# 05_CIS.net
KiCad netlist of a schematic drawn in Altium Designer
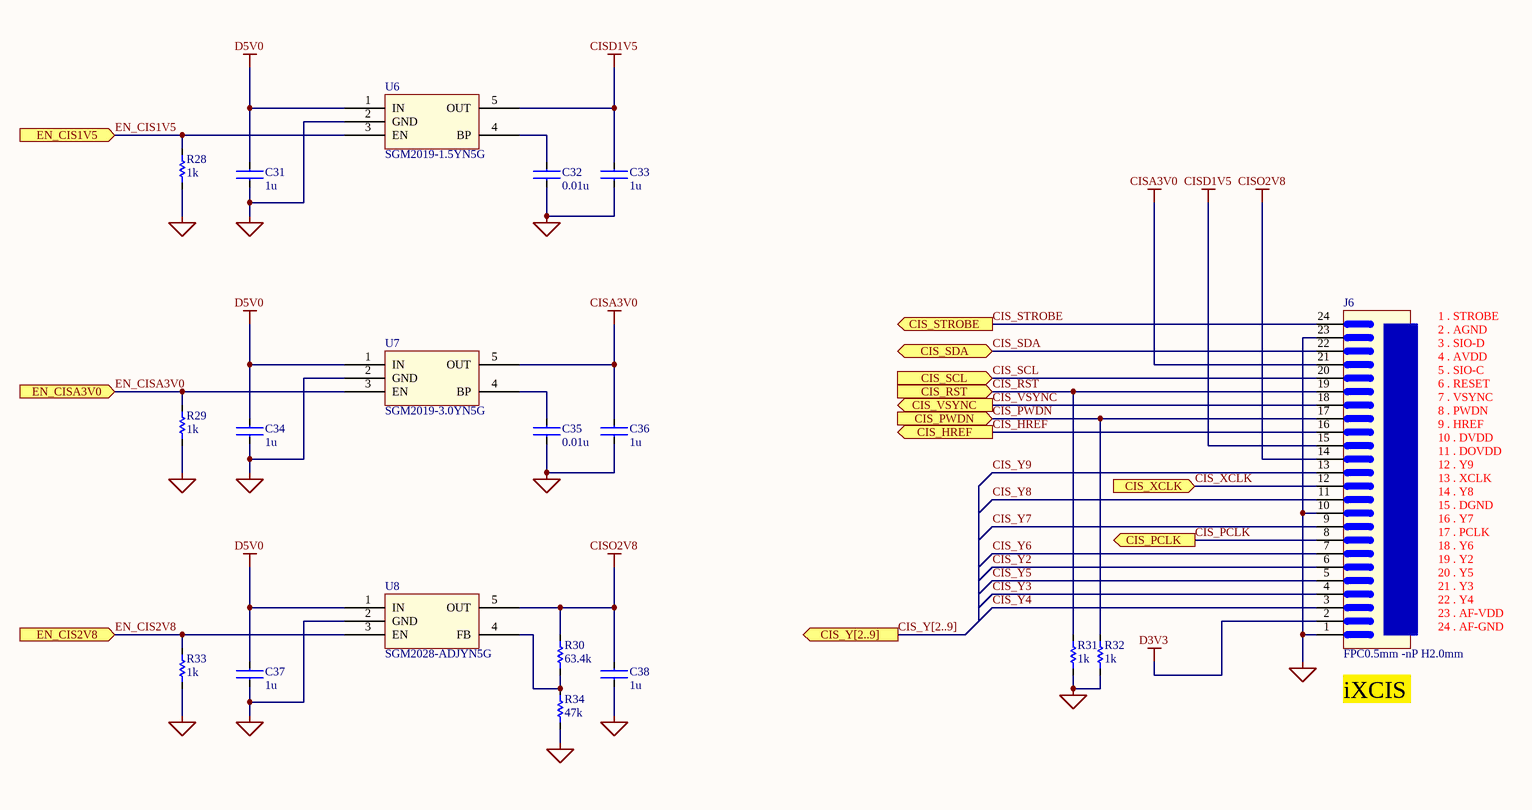
[diagram p0: 05_CIS.SchDoc]

(export (version "E")
  (design (tool "Eeschema 10.0.6"))
  (components
    (comp (ref "C31")
      (value "1u")
      (footprint "CAPC1608X09N_C0603")
      (description "CAP,Ceramic,X7R,10%,16V,1uF,0603")
      (libsource (lib "C0603") (part "CAP12"))
    )
    (comp (ref "C32")
      (value "0.01u")
      (footprint "C0402")
      (description "CAP,Ceramic,X7R,10%,16V,0.01uF,0402")
      (libsource (lib "C0402") (part "CAP0112"))
    )
    (comp (ref "C33")
      (value "1u")
      (footprint "CAPC1608X09N_C0603")
      (description "CAP,Ceramic,X7R,10%,16V,1uF,0603")
      (libsource (lib "AD15_libpkg") (part "CAP12"))
    )
    (comp (ref "C34")
      (value "1u")
      (footprint "CAPC1608X09N_C0603")
      (description "CAP,Ceramic,X7R,10%,16V,1uF,0603")
      (libsource (lib "C0603") (part "CAP12"))
    )
    (comp (ref "C35")
      (value "0.01u")
      (footprint "C0402")
      (description "CAP,Ceramic,X7R,10%,16V,0.01uF,0402")
      (libsource (lib "C0402") (part "CAP0112"))
    )
    (comp (ref "C36")
      (value "1u")
      (footprint "CAPC1608X09N_C0603")
      (description "CAP,Ceramic,X7R,10%,16V,1uF,0603")
      (libsource (lib "AD15_libpkg") (part "CAP12"))
    )
    (comp (ref "C37")
      (value "1u")
      (footprint "CAPC1608X09N_C0603")
      (description "CAP,Ceramic,X7R,10%,16V,1uF,0603")
      (libsource (lib "C0603") (part "CAP12"))
    )
    (comp (ref "C38")
      (value "1u")
      (footprint "CAPC1608X09N_C0603")
      (description "CAP,Ceramic,X7R,10%,16V,1uF,0603")
      (libsource (lib "AD15_libpkg") (part "CAP12"))
    )
    (comp (ref "J6")
      (value "FPC0.5mm -nP H2.0mm")
      (footprint "FPC0.5mm-nPH2.0mm")
      (description "FFC socket,24-Pin,bottom contact,0.5mm Pitch,SMD")
      (libsource (lib "AD15_libpkg") (part "FPC0.5mm_02"))
    )
    (comp (ref "R28")
      (value "1k")
      (footprint "R0402")
      (description "RES,1k,1%,1/16W,0402")
      (libsource (lib "R0402") (part "RES011"))
    )
    (comp (ref "R29")
      (value "1k")
      (footprint "R0402")
      (description "RES,1k,1%,1/16W,0402")
      (libsource (lib "R0402") (part "RES011"))
    )
    (comp (ref "R30")
      (value "63.4k")
      (footprint "R0402")
      (description "RES,63.4k,1%,1/16W,0402")
      (libsource (lib "R0402") (part "RES0126"))
    )
    (comp (ref "R31")
      (value "1k")
      (footprint "R0402")
      (description "RES,1k,1%,1/16W,0402")
      (libsource (lib "R0402") (part "RES011"))
    )
    (comp (ref "R32")
      (value "1k")
      (footprint "R0402")
      (description "RES,1k,1%,1/16W,0402")
      (libsource (lib "R0402") (part "RES011"))
    )
    (comp (ref "R33")
      (value "1k")
      (footprint "R0402")
      (description "RES,1k,1%,1/16W,0402")
      (libsource (lib "R0402") (part "RES011"))
    )
    (comp (ref "R34")
      (value "47k")
      (footprint "R0402")
      (description "RES,47k,1%,1/16W,0402")
      (libsource (lib "R0402") (part "RES0127"))
    )
    (comp (ref "U6")
      (value "SGM2019-1.5YN5G")
      (footprint "SOT95P280X125-5N_SGM2019")
      (description "IC,LDO 1.5V@300mA,SOT23-5")
      (libsource (lib "AD15_libpkg") (part "SGM2019-1.5"))
    )
    (comp (ref "U7")
      (value "SGM2019-3.0YN5G")
      (footprint "SOT95P280X125-5N_SGM2019")
      (description "IC,LDO 3.0V@300mA,SOT23-5")
      (libsource (lib "AD15_libpkg") (part "SGM2019-3.0"))
    )
    (comp (ref "U8")
      (value "SGM2028-ADJYN5G")
      (footprint "SOT95P280X125-5N_SGM2028")
      (description "IC,LDO 500mA,Adjustable,SOT23-5")
      (libsource (lib "AD15_libpkg") (part "SGM2028-ADJ"))
    )
  )
  (nets
    (net (code "1") (name "/CIS_HREF") (class "Default")
      (node (ref "J6") (pin "16") (pinfunction "16_16") (pintype "passive"))
    )
    (net (code "2") (name "/CIS_PCLK") (class "Default")
      (node (ref "J6") (pin "8") (pinfunction "7_8") (pintype "passive"))
    )
    (net (code "3") (name "/CIS_PWDN") (class "Default")
      (node (ref "J6") (pin "17") (pinfunction "17_17") (pintype "passive"))
      (node (ref "R32") (pin "2") (pinfunction "2_2") (pintype "passive"))
    )
    (net (code "4") (name "/CIS_RST") (class "Default")
      (node (ref "J6") (pin "19") (pinfunction "19_19") (pintype "passive"))
      (node (ref "R31") (pin "2") (pinfunction "2_2") (pintype "passive"))
    )
    (net (code "5") (name "/CIS_SCL") (class "Default")
      (node (ref "J6") (pin "20") (pinfunction "20_20") (pintype "passive"))
    )
    (net (code "6") (name "/CIS_SDA") (class "Default")
      (node (ref "J6") (pin "22") (pinfunction "22_22") (pintype "passive"))
    )
    (net (code "7") (name "/CIS_STROBE") (class "Default")
      (node (ref "J6") (pin "24") (pinfunction "24_24") (pintype "passive"))
    )
    (net (code "8") (name "/CIS_VSYNC") (class "Default")
      (node (ref "J6") (pin "18") (pinfunction "18_18") (pintype "passive"))
    )
    (net (code "9") (name "/CIS_XCLK") (class "Default")
      (node (ref "J6") (pin "12") (pinfunction "12_12") (pintype "passive"))
    )
    (net (code "10") (name "/CIS_Y2") (class "Default")
      (node (ref "J6") (pin "6") (pinfunction "5_6") (pintype "passive"))
    )
    (net (code "11") (name "/CIS_Y3") (class "Default")
      (node (ref "J6") (pin "4") (pinfunction "3_4") (pintype "passive"))
    )
    (net (code "12") (name "/CIS_Y4") (class "Default")
      (node (ref "J6") (pin "3") (pinfunction "2_3") (pintype "passive"))
    )
    (net (code "13") (name "/CIS_Y5") (class "Default")
      (node (ref "J6") (pin "5") (pinfunction "4_5") (pintype "passive"))
    )
    (net (code "14") (name "/CIS_Y6") (class "Default")
      (node (ref "J6") (pin "7") (pinfunction "6_7") (pintype "passive"))
    )
    (net (code "15") (name "/CIS_Y7") (class "Default")
      (node (ref "J6") (pin "9") (pinfunction "8_9") (pintype "passive"))
    )
    (net (code "16") (name "/CIS_Y8") (class "Default")
      (node (ref "J6") (pin "11") (pinfunction "11_11") (pintype "passive"))
    )
    (net (code "17") (name "/CIS_Y9") (class "Default")
      (node (ref "J6") (pin "13") (pinfunction "13_13") (pintype "passive"))
    )
    (net (code "19") (name "/EN_CIS1V5") (class "Default")
      (node (ref "R28") (pin "2") (pinfunction "2_2") (pintype "passive"))
      (node (ref "U6") (pin "3") (pinfunction "EN_3") (pintype "passive"))
    )
    (net (code "20") (name "/EN_CIS2V8") (class "Default")
      (node (ref "R33") (pin "2") (pinfunction "2_2") (pintype "passive"))
      (node (ref "U8") (pin "3") (pinfunction "EN_3") (pintype "passive"))
    )
    (net (code "21") (name "/EN_CISA3V0") (class "Default")
      (node (ref "R29") (pin "2") (pinfunction "2_2") (pintype "passive"))
      (node (ref "U7") (pin "3") (pinfunction "EN_3") (pintype "passive"))
    )
    (net (code "22") (name "CISA3V0") (class "Default")
      (node (ref "C36") (pin "1") (pinfunction "0_1") (pintype "passive"))
      (node (ref "J6") (pin "21") (pinfunction "21_21") (pintype "passive"))
      (node (ref "U7") (pin "5") (pinfunction "OUT_5") (pintype "passive"))
    )
    (net (code "23") (name "CISD1V5") (class "Default")
      (node (ref "C33") (pin "1") (pinfunction "0_1") (pintype "passive"))
      (node (ref "J6") (pin "15") (pinfunction "15_15") (pintype "passive"))
      (node (ref "U6") (pin "5") (pinfunction "OUT_5") (pintype "passive"))
    )
    (net (code "24") (name "CISO2V8") (class "Default")
      (node (ref "C38") (pin "1") (pinfunction "0_1") (pintype "passive"))
      (node (ref "J6") (pin "14") (pinfunction "14_14") (pintype "passive"))
      (node (ref "R30") (pin "2") (pinfunction "2_2") (pintype "passive"))
      (node (ref "U8") (pin "5") (pinfunction "OUT_5") (pintype "passive"))
    )
    (net (code "25") (name "D3V3") (class "Default")
      (node (ref "J6") (pin "2") (pinfunction "1_2") (pintype "passive"))
    )
    (net (code "26") (name "D5V0") (class "Default")
      (node (ref "C31") (pin "1") (pinfunction "0_1") (pintype "passive"))
      (node (ref "C34") (pin "1") (pinfunction "0_1") (pintype "passive"))
      (node (ref "C37") (pin "1") (pinfunction "0_1") (pintype "passive"))
      (node (ref "U6") (pin "1") (pinfunction "IN_1") (pintype "passive"))
      (node (ref "U7") (pin "1") (pinfunction "IN_1") (pintype "passive"))
      (node (ref "U8") (pin "1") (pinfunction "IN_1") (pintype "passive"))
    )
    (net (code "27") (name "GND") (class "Default")
      (node (ref "C31") (pin "2") (pinfunction "1_2") (pintype "passive"))
      (node (ref "C32") (pin "2") (pinfunction "1_2") (pintype "passive"))
      (node (ref "C33") (pin "2") (pinfunction "1_2") (pintype "passive"))
      (node (ref "C34") (pin "2") (pinfunction "1_2") (pintype "passive"))
      (node (ref "C35") (pin "2") (pinfunction "1_2") (pintype "passive"))
      (node (ref "C36") (pin "2") (pinfunction "1_2") (pintype "passive"))
      (node (ref "C37") (pin "2") (pinfunction "1_2") (pintype "passive"))
      (node (ref "C38") (pin "2") (pinfunction "1_2") (pintype "passive"))
      (node (ref "J6") (pin "1") (pinfunction "0_1") (pintype "passive"))
      (node (ref "J6") (pin "10") (pinfunction "9_10") (pintype "passive"))
      (node (ref "J6") (pin "23") (pinfunction "23_23") (pintype "passive"))
      (node (ref "R28") (pin "1") (pinfunction "0_1") (pintype "passive"))
      (node (ref "R29") (pin "1") (pinfunction "0_1") (pintype "passive"))
      (node (ref "R31") (pin "1") (pinfunction "0_1") (pintype "passive"))
      (node (ref "R32") (pin "1") (pinfunction "0_1") (pintype "passive"))
      (node (ref "R33") (pin "1") (pinfunction "0_1") (pintype "passive"))
      (node (ref "R34") (pin "1") (pinfunction "0_1") (pintype "passive"))
      (node (ref "U6") (pin "2") (pinfunction "GND_2") (pintype "passive"))
      (node (ref "U7") (pin "2") (pinfunction "GND_2") (pintype "passive"))
      (node (ref "U8") (pin "2") (pinfunction "GND_2") (pintype "passive"))
    )
    (net (code "28") (name "Net-(C32-0)") (class "Default")
      (node (ref "C32") (pin "1") (pinfunction "0_1") (pintype "passive"))
      (node (ref "U6") (pin "4") (pinfunction "BP_4") (pintype "passive"))
    )
    (net (code "29") (name "Net-(C35-0)") (class "Default")
      (node (ref "C35") (pin "1") (pinfunction "0_1") (pintype "passive"))
      (node (ref "U7") (pin "4") (pinfunction "BP_4") (pintype "passive"))
    )
    (net (code "30") (name "Net-(R30-0)") (class "Default")
      (node (ref "R30") (pin "1") (pinfunction "0_1") (pintype "passive"))
      (node (ref "R34") (pin "2") (pinfunction "2_2") (pintype "passive"))
      (node (ref "U8") (pin "4") (pinfunction "FB_4") (pintype "passive"))
    )
  )
)
